# DM1098OAKW_IMU.net
KiCad netlist of a schematic drawn in Altium Designer
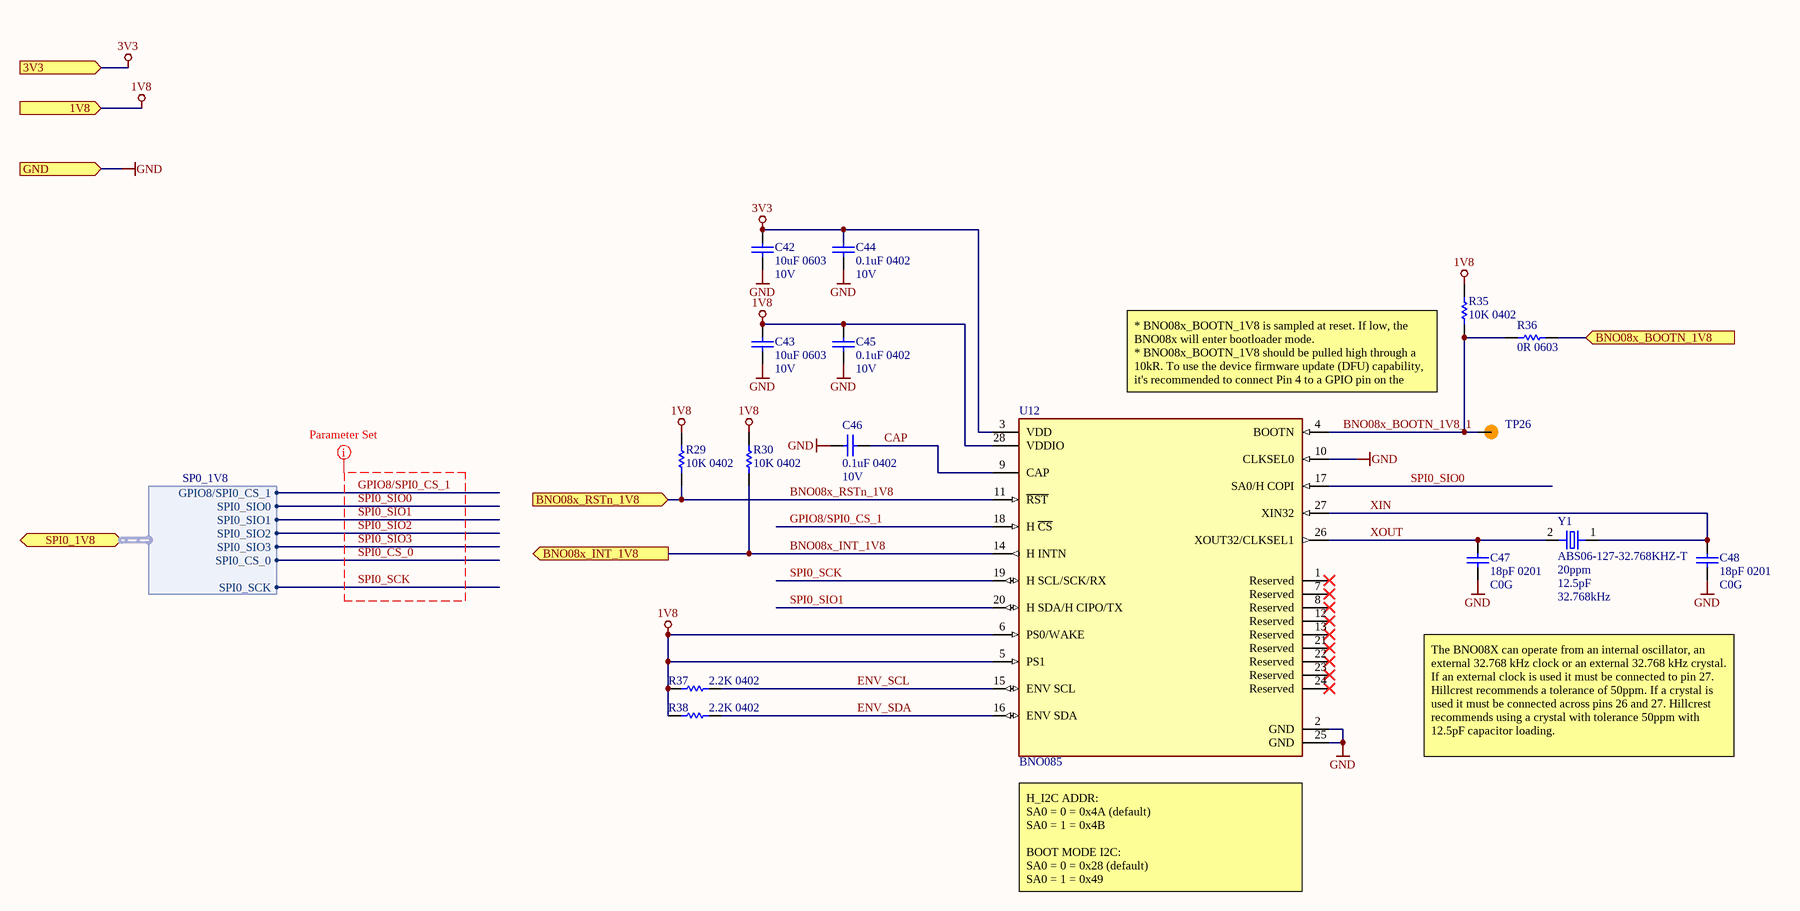
[diagram p0: DM1098OAKW_IMU.SchDoc]

(export (version "E")
  (design (tool "Eeschema 10.0.6"))
  (components
    (comp (ref "C42")
      (value "10uF 0603")
      (footprint "CAP_Altium_Vault_Generic:CAPC0603(1608)100_N")
      (description "CAP CER 10UF 10V X5R 0603 20%")
      (fields (field (name "TOLERANCE") "20%") (field (name "VOLTAGE RATING") "10V"))
      (libsource (lib "LuxonisMaster") (part "GRM188R61A106ME69D"))
    )
    (comp (ref "C43")
      (value "10uF 0603")
      (footprint "CAP_Altium_Vault_Generic:CAPC0603(1608)100_N")
      (description "CAP CER 10UF 10V X5R 0603 20%")
      (fields (field (name "TOLERANCE") "20%") (field (name "VOLTAGE RATING") "10V"))
      (libsource (lib "LuxonisMaster") (part "GRM188R61A106ME69D"))
    )
    (comp (ref "C44")
      (value "0.1uF 0402")
      (footprint "CAP_Altium_Vault_Generic:CAPC0402(1005)70_N")
      (description "CAP CER 0.1UF 10V X7R 0402 5%")
      (fields (field (name "TOLERANCE") "5%") (field (name "VOLTAGE RATING") "10V"))
      (libsource (lib "LuxonisMaster") (part "GRM155R71A104JA01D"))
    )
    (comp (ref "C45")
      (value "0.1uF 0402")
      (footprint "CAP_Altium_Vault_Generic:CAPC0402(1005)70_N")
      (description "CAP CER 0.1UF 10V X7R 0402 5%")
      (fields (field (name "TOLERANCE") "5%") (field (name "VOLTAGE RATING") "10V"))
      (libsource (lib "LuxonisMaster") (part "GRM155R71A104JA01D"))
    )
    (comp (ref "C46")
      (value "0.1uF 0402")
      (footprint "CAP_Altium_Vault_Generic:CAPC0402(1005)70_N")
      (description "CAP CER 0.1UF 10V X7R 0402 5%")
      (fields (field (name "TOLERANCE") "5%") (field (name "VOLTAGE RATING") "10V"))
      (libsource (lib "LuxonisMaster") (part "GRM155R71A104JA01D"))
    )
    (comp (ref "C47")
      (value "18pF 0201")
      (footprint "CAP_Altium_Vault_Generic:CAPC0201(0603)33_N")
      (description "Cap Ceramic 18pF 25V C0G 1% Pad SMD 0201 125C T/R")
      (fields (field (name "TOLERANCE") "1%") (field (name "DIELECTRIC") "C0G"))
      (libsource (lib "BW1092_R0M0E0") (part "GRM0335C1E180FA01D"))
    )
    (comp (ref "C48")
      (value "18pF 0201")
      (footprint "CAP_Altium_Vault_Generic:CAPC0201(0603)33_N")
      (description "Cap Ceramic 18pF 25V C0G 1% Pad SMD 0201 125C T/R")
      (fields (field (name "TOLERANCE") "1%") (field (name "DIELECTRIC") "C0G"))
      (libsource (lib "BW1092_R0M0E0") (part "GRM0335C1E180FA01D"))
    )
    (comp (ref "R29")
      (value "10K 0402")
      (footprint "RES_Altium_Vault_Generic:RESC0402(1005)_N")
      (fields (field (name "TOLERANCE") "1%"))
      (libsource (lib "LuxonisMaster") (part "RC0402FR-1310KL"))
    )
    (comp (ref "R30")
      (value "10K 0402")
      (footprint "RES_Altium_Vault_Generic:RESC0402(1005)_N")
      (fields (field (name "TOLERANCE") "1%"))
      (libsource (lib "LuxonisMaster") (part "RC0402FR-1310KL"))
    )
    (comp (ref "R35")
      (value "10K 0402")
      (footprint "RES_Altium_Vault_Generic:RESC0402(1005)_N")
      (fields (field (name "TOLERANCE") "1%"))
      (libsource (lib "LuxonisMaster") (part "RC0402FR-1310KL"))
    )
    (comp (ref "R36")
      (value "0R 0603")
      (footprint "RES_Altium_Vault_Generic:RESC0603(1608)_N")
      (fields (field (name "TOLERANCE") "5%"))
      (libsource (lib "LuxonisMaster") (part "CRCW06030000Z0EA"))
    )
    (comp (ref "R37")
      (value "2.2K 0402")
      (footprint "RES_Altium_Vault_Generic:RESC0402(1005)_N")
      (description "RES SMD 2.2K OHM 1% 1/16W 0402")
      (fields (field (name "TOLERANCE") "1%"))
      (libsource (lib "LuxonisMaster") (part "RC0402FR-072K2L"))
    )
    (comp (ref "R38")
      (value "2.2K 0402")
      (footprint "RES_Altium_Vault_Generic:RESC0402(1005)_N")
      (description "RES SMD 2.2K OHM 1% 1/16W 0402")
      (fields (field (name "TOLERANCE") "1%"))
      (libsource (lib "LuxonisMaster") (part "RC0402FR-072K2L"))
    )
    (comp (ref "TP26")
      (value "TP100_200_NS")
      (footprint "LuxonisMaster:TP100_200_NS")
      (libsource (lib "LuxonisMaster") (part "TEST_POINT"))
    )
    (comp (ref "U12")
      (value "BNO085")
      (footprint "BW1092_R0M0E0:BNO085")
      (description "IMU ACCEL/GYRO/MAG I2C 32BIT")
      (libsource (lib "BW1092_R0M0E0") (part "BNO085"))
    )
    (comp (ref "Y1")
      (value "ABS06-127-32.768KHZ-T")
      (footprint "BW1092_R0M0E0:ABS06-127-32.768KHZ-T")
      (description "CRYSTAL 32.768kHz ±20ppm Crystal 12.5pF 90 kOhms 2-SMD, No Lead")
      (fields
        (field (name "FREQUENCY TOLERANCE") "20ppm")
        (field (name "LOAD CAPACITANCE") "12.5pF")
        (field (name "FREQUENCY") "32.768kHz")
      )
      (libsource (lib "BW1092_R0M0E0") (part "ABS06-127-32.768KHZ-T"))
    )
  )
  (nets
    (net (code "2") (name "/BNO08x_BOOTN_1V8") (class "Default")
      (node (ref "R36") (pin "2") (pinfunction "2_2") (pintype "passive"))
    )
    (net (code "3") (name "/BNO08x_BOOTN_1V8_1") (class "Default")
      (node (ref "R35") (pin "1") (pinfunction "1_1") (pintype "passive"))
      (node (ref "R36") (pin "1") (pinfunction "1_1") (pintype "passive"))
      (node (ref "TP26") (pin "1") (pintype "passive"))
      (node (ref "U12") (pin "4") (pinfunction "BOOTN_4") (pintype "input"))
    )
    (net (code "4") (name "/BNO08x_INT_1V8") (class "Default")
      (node (ref "R30") (pin "1") (pinfunction "1_1") (pintype "passive"))
      (node (ref "U12") (pin "14") (pinfunction "H_INTN_14") (pintype "output"))
    )
    (net (code "5") (name "/BNO08x_RSTn_1V8") (class "Default")
      (node (ref "R29") (pin "1") (pinfunction "1_1") (pintype "passive"))
      (node (ref "U12") (pin "11") (pinfunction "~{RST}_11") (pintype "input"))
    )
    (net (code "6") (name "/CAP") (class "Default")
      (node (ref "C46") (pin "1") (pinfunction "1_1") (pintype "passive"))
      (node (ref "U12") (pin "9") (pinfunction "CAP_9") (pintype "passive"))
    )
    (net (code "7") (name "/ENV_SCL") (class "Default")
      (node (ref "R37") (pin "2") (pinfunction "2_2") (pintype "passive"))
      (node (ref "U12") (pin "15") (pinfunction "ENV_SCL_15") (pintype "bidirectional"))
    )
    (net (code "8") (name "/ENV_SDA") (class "Default")
      (node (ref "R38") (pin "2") (pinfunction "2_2") (pintype "passive"))
      (node (ref "U12") (pin "16") (pinfunction "ENV_SDA_16") (pintype "bidirectional"))
    )
    (net (code "9") (name "/GPIO8{slash}SPI0_CS_1") (class "Default")
      (node (ref "U12") (pin "18") (pinfunction "H_~{CS}_18") (pintype "input"))
    )
    (net (code "11") (name "/SPI0_SCK") (class "Default")
      (node (ref "U12") (pin "19") (pinfunction "H_SCL/SCK/RX_19") (pintype "bidirectional"))
    )
    (net (code "12") (name "/SPI0_SIO0") (class "Default")
      (node (ref "U12") (pin "17") (pinfunction "SA0/H_COPI_17") (pintype "input"))
    )
    (net (code "13") (name "/SPI0_SIO1") (class "Default")
      (node (ref "U12") (pin "20") (pinfunction "H_SDA/H_CIPO/TX_20") (pintype "bidirectional"))
    )
    (net (code "16") (name "/XIN") (class "Default")
      (node (ref "C48") (pin "2") (pinfunction "2_2") (pintype "passive"))
      (node (ref "U12") (pin "27") (pinfunction "XIN32_27") (pintype "input"))
      (node (ref "Y1") (pin "1") (pinfunction "1_1") (pintype "passive"))
    )
    (net (code "17") (name "/XOUT") (class "Default")
      (node (ref "C47") (pin "2") (pinfunction "2_2") (pintype "passive"))
      (node (ref "U12") (pin "26") (pinfunction "XOUT32/CLKSEL1_26") (pintype "output"))
      (node (ref "Y1") (pin "2") (pinfunction "2_2") (pintype "passive"))
    )
    (net (code "19") (name "1V8") (class "Default")
      (node (ref "C43") (pin "2") (pinfunction "2_2") (pintype "passive"))
      (node (ref "C45") (pin "2") (pinfunction "2_2") (pintype "passive"))
      (node (ref "R29") (pin "2") (pinfunction "2_2") (pintype "passive"))
      (node (ref "R30") (pin "2") (pinfunction "2_2") (pintype "passive"))
      (node (ref "R35") (pin "2") (pinfunction "2_2") (pintype "passive"))
      (node (ref "R37") (pin "1") (pinfunction "1_1") (pintype "passive"))
      (node (ref "R38") (pin "1") (pinfunction "1_1") (pintype "passive"))
      (node (ref "U12") (pin "28") (pinfunction "VDDIO_28") (pintype "power_in"))
      (node (ref "U12") (pin "5") (pinfunction "PS1_5") (pintype "input"))
      (node (ref "U12") (pin "6") (pinfunction "PS0/WAKE_6") (pintype "input"))
    )
    (net (code "20") (name "3V3") (class "Default")
      (node (ref "C42") (pin "2") (pinfunction "2_2") (pintype "passive"))
      (node (ref "C44") (pin "2") (pinfunction "2_2") (pintype "passive"))
      (node (ref "U12") (pin "3") (pinfunction "VDD_3") (pintype "power_in"))
    )
    (net (code "21") (name "GND") (class "Default")
      (node (ref "C42") (pin "1") (pinfunction "1_1") (pintype "passive"))
      (node (ref "C43") (pin "1") (pinfunction "1_1") (pintype "passive"))
      (node (ref "C44") (pin "1") (pinfunction "1_1") (pintype "passive"))
      (node (ref "C45") (pin "1") (pinfunction "1_1") (pintype "passive"))
      (node (ref "C46") (pin "2") (pinfunction "2_2") (pintype "passive"))
      (node (ref "C47") (pin "1") (pinfunction "1_1") (pintype "passive"))
      (node (ref "C48") (pin "1") (pinfunction "1_1") (pintype "passive"))
      (node (ref "U12") (pin "10") (pinfunction "CLKSEL0_10") (pintype "input"))
      (node (ref "U12") (pin "2") (pinfunction "GND_2") (pintype "power_in"))
      (node (ref "U12") (pin "25") (pinfunction "GND_25") (pintype "power_in"))
    )
    (net (code "22") (name "unconnected-(U12-Reserved-Pad1)") (class "Default")
      (node (ref "U12") (pin "1") (pinfunction "Reserved_1") (pintype "passive+no_connect"))
    )
    (net (code "23") (name "unconnected-(U12-Reserved-Pad7)") (class "Default")
      (node (ref "U12") (pin "7") (pinfunction "Reserved_7") (pintype "passive+no_connect"))
    )
    (net (code "24") (name "unconnected-(U12-Reserved-Pad8)") (class "Default")
      (node (ref "U12") (pin "8") (pinfunction "Reserved_8") (pintype "passive+no_connect"))
    )
    (net (code "25") (name "unconnected-(U12-Reserved-Pad12)") (class "Default")
      (node (ref "U12") (pin "12") (pinfunction "Reserved_12") (pintype "passive+no_connect"))
    )
    (net (code "26") (name "unconnected-(U12-Reserved-Pad13)") (class "Default")
      (node (ref "U12") (pin "13") (pinfunction "Reserved_13") (pintype "passive+no_connect"))
    )
    (net (code "27") (name "unconnected-(U12-Reserved-Pad21)") (class "Default")
      (node (ref "U12") (pin "21") (pinfunction "Reserved_21") (pintype "passive+no_connect"))
    )
    (net (code "28") (name "unconnected-(U12-Reserved-Pad22)") (class "Default")
      (node (ref "U12") (pin "22") (pinfunction "Reserved_22") (pintype "passive+no_connect"))
    )
    (net (code "29") (name "unconnected-(U12-Reserved-Pad23)") (class "Default")
      (node (ref "U12") (pin "23") (pinfunction "Reserved_23") (pintype "passive+no_connect"))
    )
    (net (code "30") (name "unconnected-(U12-Reserved-Pad24)") (class "Default")
      (node (ref "U12") (pin "24") (pinfunction "Reserved_24") (pintype "passive+no_connect"))
    )
  )
)
